# ME433_board.net
KiCad netlist of a schematic drawn in EAGLE
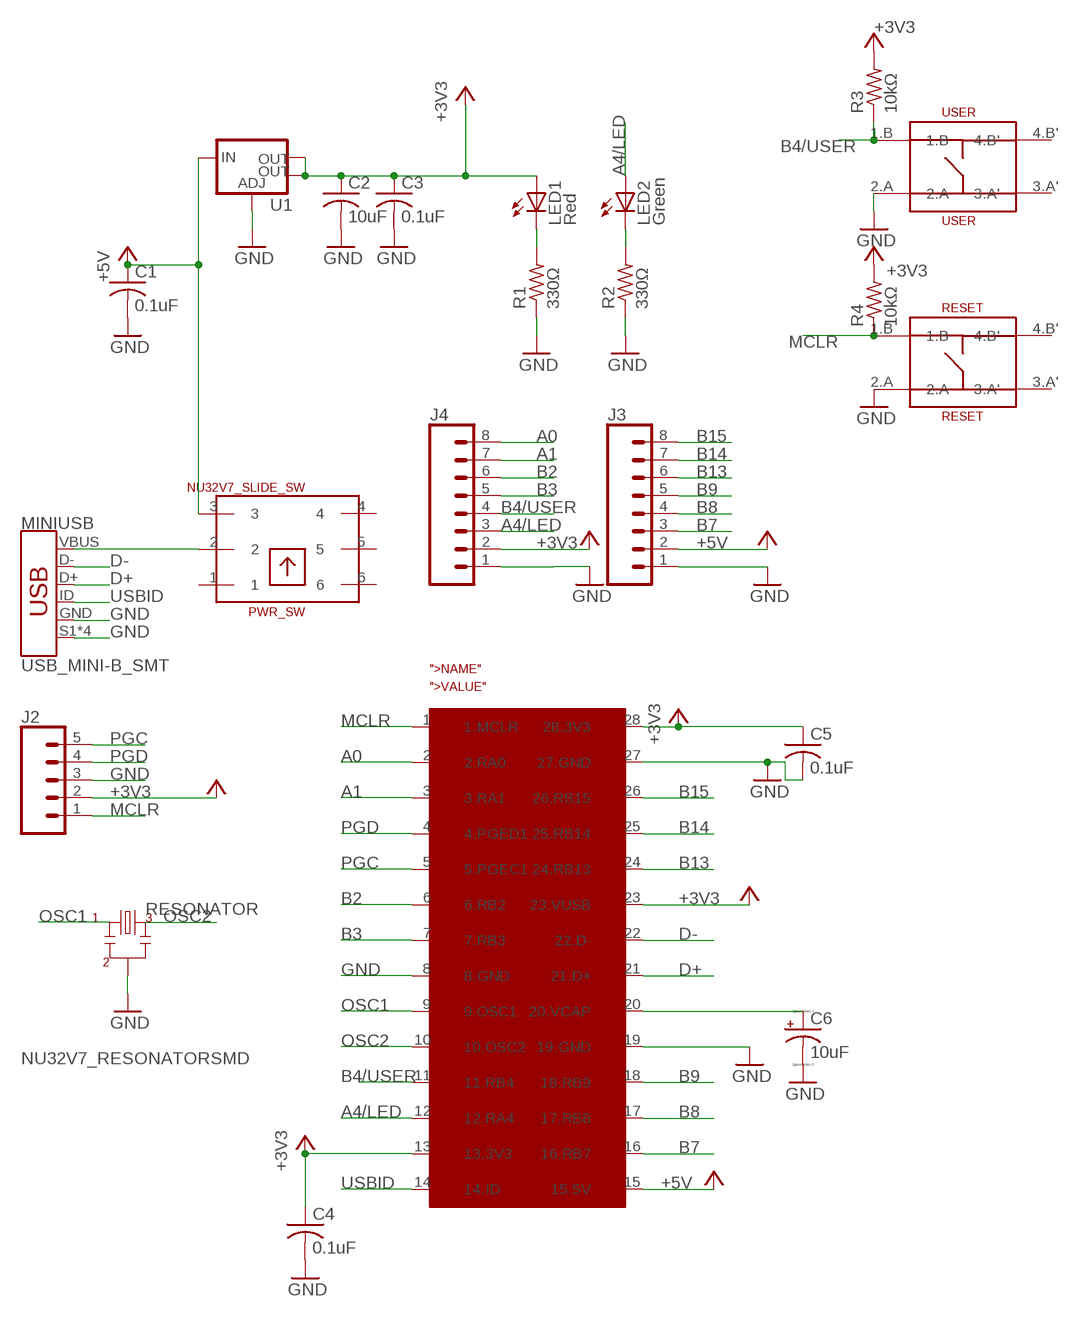
[diagram p0: schematic, sheet 1]

(export (version "E")
  (design (tool "Eeschema 10.0.6"))
  (components
    (comp (ref "C1")
      (value "0.1uF")
      (footprint "eagle-import:C0603")
      (libsource (lib "eagle-import") (part "C-USC0603"))
    )
    (comp (ref "C2")
      (value "10uF")
      (footprint "eagle-import:C0603")
      (libsource (lib "eagle-import") (part "C-USC0603"))
    )
    (comp (ref "C3")
      (value "0.1uF")
      (footprint "eagle-import:C0603")
      (libsource (lib "eagle-import") (part "C-USC0603"))
    )
    (comp (ref "C4")
      (value "0.1uF")
      (footprint "eagle-import:C0603")
      (libsource (lib "eagle-import") (part "C-USC0603"))
    )
    (comp (ref "C5")
      (value "0.1uF")
      (footprint "eagle-import:C0603")
      (libsource (lib "eagle-import") (part "C-USC0603"))
    )
    (comp (ref "C6")
      (value "10uF")
      (footprint "eagle-import:153CLV-0605")
      (libsource (lib "eagle-import") (part "CPOL-US153CLV-0605"))
    )
    (comp (ref "J2")
      (value "CONN_05")
      (footprint "eagle-import:1X05")
      (libsource (lib "eagle-import") (part "CONN_05"))
    )
    (comp (ref "J3")
      (value "CONN_08\"")
      (footprint "eagle-import:1X08")
      (libsource (lib "eagle-import") (part "CONN_08{dblquote}"))
    )
    (comp (ref "J4")
      (value "CONN_08\"")
      (footprint "eagle-import:1X08")
      (libsource (lib "eagle-import") (part "CONN_08{dblquote}"))
    )
    (comp (ref "LED1")
      (value "Red")
      (footprint "eagle-import:SML0603")
      (libsource (lib "eagle-import") (part "LEDSML0603"))
    )
    (comp (ref "LED2")
      (value "Green")
      (footprint "eagle-import:SML0603")
      (libsource (lib "eagle-import") (part "LEDSML0603"))
    )
    (comp (ref "MINIUSB")
      (value "USB_MINI-B_SMT")
      (footprint "eagle-import:USB-MINIB")
      (libsource (lib "eagle-import") (part "USB_MINI-B_SMT"))
    )
    (comp (ref "PWR_SW")
      (value "NU32V7_SLIDE_SW")
      (footprint "eagle-import:NU32V7_SLIDE_SW")
      (libsource (lib "eagle-import") (part "NU32V7_SLIDE_SW"))
    )
    (comp (ref "R1")
      (value "330Ω")
      (footprint "eagle-import:R0603")
      (libsource (lib "eagle-import") (part "R-US_R0603"))
    )
    (comp (ref "R2")
      (value "330Ω")
      (footprint "eagle-import:R0603")
      (libsource (lib "eagle-import") (part "R-US_R0603"))
    )
    (comp (ref "R3")
      (value "10kΩ")
      (footprint "eagle-import:R0603")
      (libsource (lib "eagle-import") (part "R-US_R0603"))
    )
    (comp (ref "R4")
      (value "10kΩ")
      (footprint "eagle-import:R0603")
      (libsource (lib "eagle-import") (part "R-US_R0603"))
    )
    (comp (ref "RESET")
      (value "RESET")
      (footprint "eagle-import:NU32V7_MOM_SW")
      (libsource (lib "eagle-import") (part "NU32V7_MOM_SW"))
    )
    (comp (ref "RESONATOR")
      (value "NU32V7_RESONATORSMD")
      (footprint "eagle-import:NU32V7_RESONATOR-SMD")
      (libsource (lib "eagle-import") (part "NU32V7_RESONATORSMD"))
    )
    (comp (ref "U$1")
      (value "PIC32")
      (footprint "eagle-import:DIL28-3")
      (libsource (lib "eagle-import") (part "PIC32"))
    )
    (comp (ref "U1")
      (value "NU32V7_V_REG_LM1117SOT223")
      (footprint "eagle-import:NU32V7_SOT223")
      (libsource (lib "eagle-import") (part "NU32V7_V_REG_LM1117SOT223"))
    )
    (comp (ref "USER")
      (value "USER")
      (footprint "eagle-import:NU32V7_MOM_SW")
      (libsource (lib "eagle-import") (part "NU32V7_MOM_SW"))
    )
  )
  (nets
    (net (code "1") (name "+3V3") (class "Default")
      (node (ref "C2") (pin "1") (pinfunction "1_1") (pintype "passive"))
      (node (ref "C3") (pin "1") (pinfunction "1_1") (pintype "passive"))
      (node (ref "C4") (pin "1") (pinfunction "1_1") (pintype "passive"))
      (node (ref "C5") (pin "1") (pinfunction "1_1") (pintype "passive"))
      (node (ref "J2") (pin "2") (pinfunction "2_2") (pintype "passive"))
      (node (ref "J4") (pin "2") (pinfunction "2_2") (pintype "passive"))
      (node (ref "LED1") (pin "A") (pinfunction "A_A") (pintype "passive"))
      (node (ref "R3") (pin "2") (pinfunction "2_2") (pintype "passive"))
      (node (ref "R4") (pin "2") (pinfunction "2_2") (pintype "passive"))
      (node (ref "U$1") (pin "13") (pinfunction "13.3V3_13") (pintype "bidirectional"))
      (node (ref "U$1") (pin "23") (pinfunction "23.VUSB_23") (pintype "bidirectional"))
      (node (ref "U$1") (pin "28") (pinfunction "28.3V3_28") (pintype "bidirectional"))
      (node (ref "U1") (pin "2") (pinfunction "OUT_2") (pintype "output"))
      (node (ref "U1") (pin "4") (pinfunction "OUT_4") (pintype "output"))
    )
    (net (code "2") (name "+5V") (class "Default")
      (node (ref "C1") (pin "1") (pinfunction "1_1") (pintype "passive"))
      (node (ref "J3") (pin "2") (pinfunction "2_2") (pintype "passive"))
      (node (ref "PWR_SW") (pin "3") (pinfunction "3_3") (pintype "bidirectional"))
      (node (ref "U$1") (pin "15") (pinfunction "15.5V_15") (pintype "bidirectional"))
      (node (ref "U1") (pin "3") (pinfunction "IN_3") (pintype "input"))
    )
    (net (code "3") (name "/A0") (class "Default")
      (node (ref "J4") (pin "8") (pinfunction "8_8") (pintype "passive"))
      (node (ref "U$1") (pin "2") (pinfunction "2.RA0_2") (pintype "bidirectional"))
    )
    (net (code "4") (name "/A1") (class "Default")
      (node (ref "J4") (pin "7") (pinfunction "7_7") (pintype "passive"))
      (node (ref "U$1") (pin "3") (pinfunction "3.RA1_3") (pintype "bidirectional"))
    )
    (net (code "5") (name "/A4{slash}LED") (class "Default")
      (node (ref "J4") (pin "3") (pinfunction "3_3") (pintype "passive"))
      (node (ref "LED2") (pin "A") (pinfunction "A_A") (pintype "passive"))
      (node (ref "U$1") (pin "12") (pinfunction "12.RA4_12") (pintype "bidirectional"))
    )
    (net (code "6") (name "/B2") (class "Default")
      (node (ref "J4") (pin "6") (pinfunction "6_6") (pintype "passive"))
      (node (ref "U$1") (pin "6") (pinfunction "6.RB2_6") (pintype "bidirectional"))
    )
    (net (code "7") (name "/B3") (class "Default")
      (node (ref "J4") (pin "5") (pinfunction "5_5") (pintype "passive"))
      (node (ref "U$1") (pin "7") (pinfunction "7.RB3_7") (pintype "bidirectional"))
    )
    (net (code "8") (name "/B4{slash}USER") (class "Default")
      (node (ref "J4") (pin "4") (pinfunction "4_4") (pintype "passive"))
      (node (ref "R3") (pin "1") (pinfunction "1_1") (pintype "passive"))
      (node (ref "U$1") (pin "11") (pinfunction "11.RB4_11") (pintype "bidirectional"))
      (node (ref "USER") (pin "1.B") (pinfunction "1.B_1.B") (pintype "bidirectional"))
    )
    (net (code "9") (name "/B7") (class "Default")
      (node (ref "J3") (pin "3") (pinfunction "3_3") (pintype "passive"))
      (node (ref "U$1") (pin "16") (pinfunction "16.RB7_16") (pintype "bidirectional"))
    )
    (net (code "10") (name "/B8") (class "Default")
      (node (ref "J3") (pin "4") (pinfunction "4_4") (pintype "passive"))
      (node (ref "U$1") (pin "17") (pinfunction "17.RB8_17") (pintype "bidirectional"))
    )
    (net (code "11") (name "/B9") (class "Default")
      (node (ref "J3") (pin "5") (pinfunction "5_5") (pintype "passive"))
      (node (ref "U$1") (pin "18") (pinfunction "18.RB9_18") (pintype "bidirectional"))
    )
    (net (code "12") (name "/B13") (class "Default")
      (node (ref "J3") (pin "6") (pinfunction "6_6") (pintype "passive"))
      (node (ref "U$1") (pin "24") (pinfunction "24.RB13_24") (pintype "bidirectional"))
    )
    (net (code "13") (name "/B14") (class "Default")
      (node (ref "J3") (pin "7") (pinfunction "7_7") (pintype "passive"))
      (node (ref "U$1") (pin "25") (pinfunction "25.RB14_25") (pintype "bidirectional"))
    )
    (net (code "14") (name "/B15") (class "Default")
      (node (ref "J3") (pin "8") (pinfunction "8_8") (pintype "passive"))
      (node (ref "U$1") (pin "26") (pinfunction "26.RB15_26") (pintype "bidirectional"))
    )
    (net (code "15") (name "/D+") (class "Default")
      (node (ref "MINIUSB") (pin "D+") (pinfunction "D+_D+") (pintype "bidirectional"))
      (node (ref "U$1") (pin "21") (pinfunction "21.D+_21") (pintype "bidirectional"))
    )
    (net (code "16") (name "/D-") (class "Default")
      (node (ref "MINIUSB") (pin "D-") (pinfunction "D-_D-") (pintype "bidirectional"))
      (node (ref "U$1") (pin "22") (pinfunction "22.D-_22") (pintype "bidirectional"))
    )
    (net (code "17") (name "/MCLR") (class "Default")
      (node (ref "J2") (pin "1") (pinfunction "1_1") (pintype "passive"))
      (node (ref "R4") (pin "1") (pinfunction "1_1") (pintype "passive"))
      (node (ref "RESET") (pin "1.B") (pinfunction "1.B_1.B") (pintype "bidirectional"))
      (node (ref "U$1") (pin "1") (pinfunction "1.MCLR_1") (pintype "bidirectional"))
    )
    (net (code "18") (name "/OSC1") (class "Default")
      (node (ref "RESONATOR") (pin "1") (pinfunction "1_1") (pintype "passive"))
      (node (ref "U$1") (pin "9") (pinfunction "9.OSC1_9") (pintype "bidirectional"))
    )
    (net (code "19") (name "/OSC2") (class "Default")
      (node (ref "RESONATOR") (pin "3") (pinfunction "3_3") (pintype "passive"))
      (node (ref "U$1") (pin "10") (pinfunction "10.OSC2_10") (pintype "bidirectional"))
    )
    (net (code "20") (name "/PGC") (class "Default")
      (node (ref "J2") (pin "5") (pinfunction "5_5") (pintype "passive"))
      (node (ref "U$1") (pin "5") (pinfunction "5.PGEC1_5") (pintype "bidirectional"))
    )
    (net (code "21") (name "/PGD") (class "Default")
      (node (ref "J2") (pin "4") (pinfunction "4_4") (pintype "passive"))
      (node (ref "U$1") (pin "4") (pinfunction "4.PGED1_4") (pintype "bidirectional"))
    )
    (net (code "22") (name "/USBID") (class "Default")
      (node (ref "MINIUSB") (pin "ID") (pinfunction "ID_ID") (pintype "bidirectional"))
      (node (ref "U$1") (pin "14") (pinfunction "14.ID_14") (pintype "bidirectional"))
    )
    (net (code "23") (name "GND") (class "Default")
      (node (ref "C1") (pin "2") (pinfunction "2_2") (pintype "passive"))
      (node (ref "C2") (pin "2") (pinfunction "2_2") (pintype "passive"))
      (node (ref "C3") (pin "2") (pinfunction "2_2") (pintype "passive"))
      (node (ref "C4") (pin "2") (pinfunction "2_2") (pintype "passive"))
      (node (ref "C5") (pin "2") (pinfunction "2_2") (pintype "passive"))
      (node (ref "C6") (pin "-") (pinfunction "-_-") (pintype "passive"))
      (node (ref "J2") (pin "3") (pinfunction "3_3") (pintype "passive"))
      (node (ref "J3") (pin "1") (pinfunction "1_1") (pintype "passive"))
      (node (ref "J4") (pin "1") (pinfunction "1_1") (pintype "passive"))
      (node (ref "MINIUSB") (pin "GND") (pinfunction "GND_GND") (pintype "power_in"))
      (node (ref "MINIUSB") (pin "S1") (pinfunction "SHIELD_S1") (pintype "bidirectional"))
      (node (ref "MINIUSB") (pin "S2") (pinfunction "SHIELD_S2") (pintype "bidirectional"))
      (node (ref "MINIUSB") (pin "S3") (pinfunction "SHIELD_S3") (pintype "bidirectional"))
      (node (ref "MINIUSB") (pin "S4") (pinfunction "SHIELD_S4") (pintype "bidirectional"))
      (node (ref "R1") (pin "1") (pinfunction "1_1") (pintype "passive"))
      (node (ref "R2") (pin "1") (pinfunction "1_1") (pintype "passive"))
      (node (ref "RESET") (pin "2.A") (pinfunction "2.A_2.A") (pintype "bidirectional"))
      (node (ref "RESONATOR") (pin "2") (pinfunction "2_2") (pintype "passive"))
      (node (ref "U$1") (pin "19") (pinfunction "19.GND_19") (pintype "bidirectional"))
      (node (ref "U$1") (pin "27") (pinfunction "27.GND_27") (pintype "bidirectional"))
      (node (ref "U$1") (pin "8") (pinfunction "8.GND_8") (pintype "bidirectional"))
      (node (ref "U1") (pin "1") (pinfunction "ADJ_1") (pintype "input"))
      (node (ref "USER") (pin "2.A") (pinfunction "2.A_2.A") (pintype "bidirectional"))
    )
    (net (code "24") (name "Net-(LED1-PadC)") (class "Default")
      (node (ref "LED1") (pin "C") (pinfunction "C_C") (pintype "passive"))
      (node (ref "R1") (pin "2") (pinfunction "2_2") (pintype "passive"))
    )
    (net (code "25") (name "Net-(LED2-PadC)") (class "Default")
      (node (ref "LED2") (pin "C") (pinfunction "C_C") (pintype "passive"))
      (node (ref "R2") (pin "2") (pinfunction "2_2") (pintype "passive"))
    )
    (net (code "26") (name "Net-(MINIUSB-PadVBUS)") (class "Default")
      (node (ref "MINIUSB") (pin "VBUS") (pinfunction "VBUS_VBUS") (pintype "power_in"))
      (node (ref "PWR_SW") (pin "2") (pinfunction "2_2") (pintype "bidirectional"))
    )
    (net (code "27") (name "Net-(U$1-20.VCAP)") (class "Default")
      (node (ref "C6") (pin "+") (pinfunction "+_+") (pintype "passive"))
      (node (ref "U$1") (pin "20") (pinfunction "20.VCAP_20") (pintype "bidirectional"))
    )
    (net (code "28") (name "unconnected-(PWR_SW-Pad1)") (class "Default")
      (node (ref "PWR_SW") (pin "1") (pinfunction "1_1") (pintype "bidirectional"))
    )
    (net (code "29") (name "unconnected-(PWR_SW-Pad4)") (class "Default")
      (node (ref "PWR_SW") (pin "4") (pinfunction "4_4") (pintype "bidirectional"))
    )
    (net (code "30") (name "unconnected-(PWR_SW-Pad5)") (class "Default")
      (node (ref "PWR_SW") (pin "5") (pinfunction "5_5") (pintype "bidirectional"))
    )
    (net (code "31") (name "unconnected-(PWR_SW-Pad6)") (class "Default")
      (node (ref "PWR_SW") (pin "6") (pinfunction "6_6") (pintype "bidirectional"))
    )
    (net (code "32") (name "unconnected-(RESET-Pad3.A')") (class "Default")
      (node (ref "RESET") (pin "3.A'") (pinfunction "3.A'_3.A'") (pintype "bidirectional"))
    )
    (net (code "33") (name "unconnected-(RESET-Pad4.B')") (class "Default")
      (node (ref "RESET") (pin "4.B'") (pinfunction "4.B'_4.B'") (pintype "bidirectional"))
    )
    (net (code "34") (name "unconnected-(USER-Pad3.A')") (class "Default")
      (node (ref "USER") (pin "3.A'") (pinfunction "3.A'_3.A'") (pintype "bidirectional"))
    )
    (net (code "35") (name "unconnected-(USER-Pad4.B')") (class "Default")
      (node (ref "USER") (pin "4.B'") (pinfunction "4.B'_4.B'") (pintype "bidirectional"))
    )
  )
)
